# SCH_G-Cacher_2026-07-06.net
KiCad netlist of a schematic drawn in EasyEDA
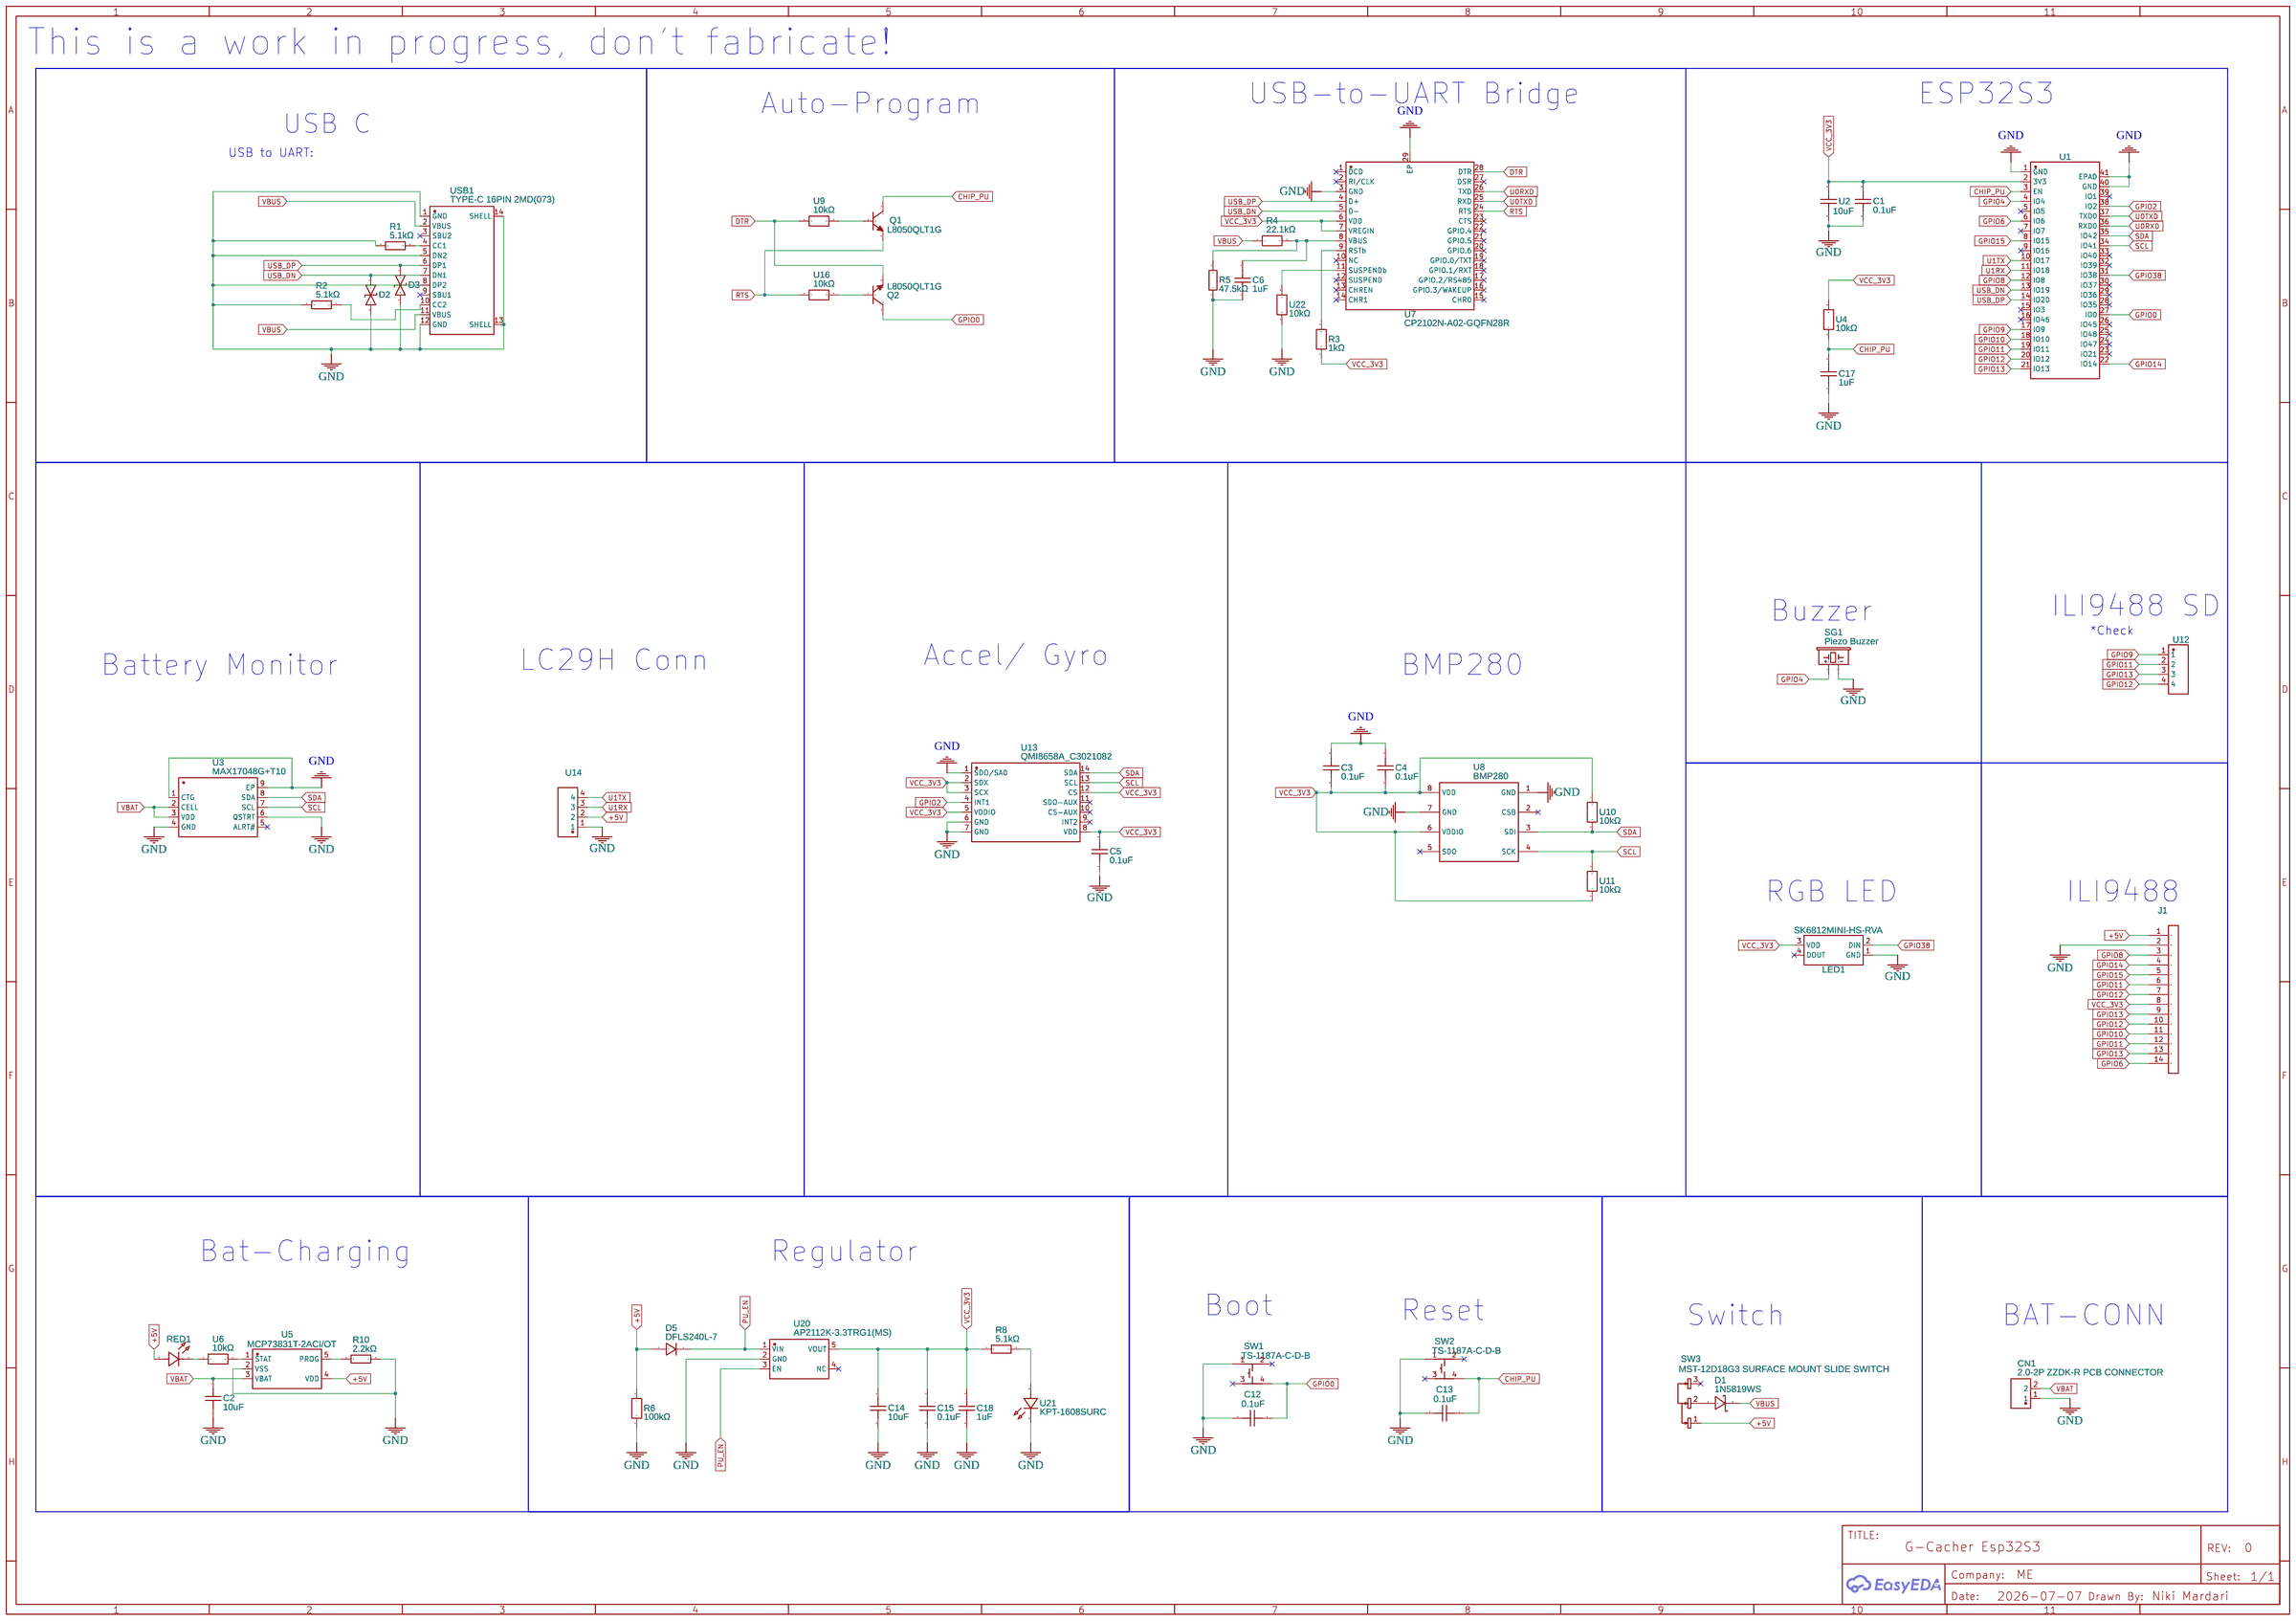
[diagram p0: schematic sheet]

(export (version "E")
  (design (tool "Eeschema 10.0.6"))
  (components
    (comp (ref "C1")
      (value "0.1uF")
      (fields (field (name "Manufacturer Part") "C1005X5R1E104M050BC") (field (name "Manufacturer") "TDK"))
      (libsource (lib "") (part "C1005X5R1E104M050BC_C3886291_1"))
    )
    (comp (ref "C2")
      (value "10uF")
      (fields (field (name "Manufacturer Part") "0603X106M100NT") (field (name "Manufacturer") "FH(风华)"))
      (libsource (lib "") (part "0603X106M100NT"))
    )
    (comp (ref "C3")
      (value "0.1uF")
      (fields (field (name "Manufacturer Part") "C1005X5R1E104M050BC") (field (name "Manufacturer") "TDK"))
      (libsource (lib "") (part "C1005X5R1E104M050BC_C3886291_1"))
    )
    (comp (ref "C4")
      (value "0.1uF")
      (fields (field (name "Manufacturer Part") "C1005X5R1E104M050BC") (field (name "Manufacturer") "TDK"))
      (libsource (lib "") (part "C1005X5R1E104M050BC_C3886291_1"))
    )
    (comp (ref "C5")
      (value "0.1uF")
      (fields (field (name "Manufacturer Part") "C1005X5R1E104M050BC") (field (name "Manufacturer") "TDK"))
      (libsource (lib "") (part "C1005X5R1E104M050BC_C3886291_1"))
    )
    (comp (ref "C6")
      (value "1uF")
      (fields (field (name "Manufacturer Part") "YNA18B3U0G105MT000N") (field (name "Manufacturer") "TDK"))
      (libsource (lib "") (part "YNA18B3U0G105MT000N"))
    )
    (comp (ref "C12")
      (value "0.1uF")
      (fields (field (name "Manufacturer Part") "C1005X5R1E104M050BC") (field (name "Manufacturer") "TDK"))
      (libsource (lib "") (part "C1005X5R1E104M050BC_C3886291"))
    )
    (comp (ref "C13")
      (value "0.1uF")
      (fields (field (name "Manufacturer Part") "C1005X5R1E104M050BC") (field (name "Manufacturer") "TDK"))
      (libsource (lib "") (part "C1005X5R1E104M050BC_C3886291"))
    )
    (comp (ref "C14")
      (value "10uF")
      (fields (field (name "Manufacturer Part") "0603X106M100NT") (field (name "Manufacturer") "FH(风华)"))
      (libsource (lib "") (part "0603X106M100NT"))
    )
    (comp (ref "C15")
      (value "0.1uF")
      (fields (field (name "Manufacturer Part") "C1005X5R1E104M050BC") (field (name "Manufacturer") "TDK"))
      (libsource (lib "") (part "C1005X5R1E104M050BC_C3886291_1"))
    )
    (comp (ref "C17")
      (value "1uF")
      (fields (field (name "Manufacturer Part") "YNA18B3U0G105MT000N") (field (name "Manufacturer") "TDK"))
      (libsource (lib "") (part "YNA18B3U0G105MT000N"))
    )
    (comp (ref "C18")
      (value "1uF")
      (fields (field (name "Manufacturer Part") "YNA18B3U0G105MT000N") (field (name "Manufacturer") "TDK"))
      (libsource (lib "") (part "YNA18B3U0G105MT000N"))
    )
    (comp (ref "CN1")
      (value "2.0-2P ZZDK-R PCB CONNECTOR")
      (fields
        (field (name "Manufacturer Part") "2.0-2P ZZDK-R PCB Connector")
        (field (name "Manufacturer") "SHOU HAN(首韩)")
      )
      (libsource (lib "") (part "2.0-2P ZZDK-R PCB CONNECTOR"))
    )
    (comp (ref "D1")
      (value "1N5819WS")
      (fields (field (name "Manufacturer") "Hottech(合科泰)"))
      (libsource (lib "") (part "1N5819WS"))
    )
    (comp (ref "D2")
      (value "LESD5D5.0CT1G")
      (fields (field (name "Manufacturer") "LRC(乐山无线电)"))
      (libsource (lib "") (part "LESD5D5.0CT1G"))
    )
    (comp (ref "D3")
      (value "LESD5D5.0CT1G")
      (fields (field (name "Manufacturer") "LRC(乐山无线电)"))
      (libsource (lib "") (part "LESD5D5.0CT1G"))
    )
    (comp (ref "D5")
      (value "DFLS240L-7")
      (fields (field (name "Manufacturer") "DIODES(美台)"))
      (libsource (lib "") (part "DFLS240L-7"))
    )
    (comp (ref "J1") (value "14 PIN FEMALE HEADER") (libsource (lib "") (part "14 PIN FEMALE HEADER")))
    (comp (ref "LED1")
      (value "SK6812MINI-HS-RVA")
      (fields (field (name "Manufacturer") "欧思科光电"))
      (libsource (lib "") (part "SK6812MINI-HS-RVA"))
    )
    (comp (ref "Q1")
      (value "L8050QLT1G")
      (fields (field (name "Manufacturer") "LRC(乐山无线电)"))
      (libsource (lib "") (part "L8050QLT1G_1"))
    )
    (comp (ref "Q2")
      (value "L8050QLT1G")
      (fields (field (name "Manufacturer") "LRC(乐山无线电)"))
      (libsource (lib "") (part "L8050QLT1G"))
    )
    (comp (ref "R1")
      (value "5.1kΩ")
      (fields
        (field (name "Manufacturer Part") "0402WGF5101TCE")
        (field (name "Manufacturer") "UNI-ROYAL(厚声)")
      )
      (libsource (lib "") (part "0402WGF5101TCE"))
    )
    (comp (ref "R2")
      (value "5.1kΩ")
      (fields
        (field (name "Manufacturer Part") "0402WGF5101TCE")
        (field (name "Manufacturer") "UNI-ROYAL(厚声)")
      )
      (libsource (lib "") (part "0402WGF5101TCE"))
    )
    (comp (ref "R3")
      (value "1kΩ")
      (fields (field (name "Manufacturer Part") "PTFR0603Q1K00N9") (field (name "Manufacturer") "RESI(开步睿思)"))
      (libsource (lib "") (part "PTFR0603Q1K00N9"))
    )
    (comp (ref "R4")
      (value "22.1kΩ")
      (fields (field (name "Manufacturer Part") "FRC0402F2212TS") (field (name "Manufacturer") "FOJAN(富捷)"))
      (libsource (lib "") (part "FRC0402F2212TS"))
    )
    (comp (ref "R5")
      (value "47.5kΩ")
      (fields (field (name "Manufacturer Part") "RC-02K4752FT") (field (name "Manufacturer") "FH(风华)"))
      (libsource (lib "") (part "RC-02K4752FT"))
    )
    (comp (ref "R6")
      (value "100kΩ")
      (fields
        (field (name "Manufacturer Part") "TR0603B100KP0525Z")
        (field (name "Manufacturer") "EVER OHMS(天二科技)")
      )
      (libsource (lib "") (part "TR0603B100KP0525Z"))
    )
    (comp (ref "R8")
      (value "5.1kΩ")
      (fields
        (field (name "Manufacturer Part") "0402WGF5101TCE")
        (field (name "Manufacturer") "UNI-ROYAL(厚声)")
      )
      (libsource (lib "") (part "0402WGF5101TCE"))
    )
    (comp (ref "R10")
      (value "2.2kΩ")
      (fields (field (name "Manufacturer Part") "RMC04022.2K5%N") (field (name "Manufacturer") "Tyohm(幸亚电阻)"))
      (libsource (lib "") (part "RMC04022.2K5%N"))
    )
    (comp (ref "RED1")
      (value "F.0603.00008/P2-0603R1TS2-06T-002")
      (fields (field (name "Manufacturer") "TUOZHAN(拓展光电)"))
      (libsource (lib "") (part "F.0603.00008/P2-0603R1TS2-06T-002"))
    )
    (comp (ref "SG1") (value "Piezo Buzzer") (libsource (lib "") (part "Piezo Buzzer")))
    (comp (ref "SW1")
      (value "TS-1187A-C-D-B")
      (fields (field (name "Manufacturer") "XKB Connection(中国星坤)"))
      (libsource (lib "") (part "TS-1187A-C-D-B"))
    )
    (comp (ref "SW2")
      (value "TS-1187A-C-D-B")
      (fields (field (name "Manufacturer") "XKB Connection(中国星坤)"))
      (libsource (lib "") (part "TS-1187A-C-D-B"))
    )
    (comp (ref "SW3")
      (value "MST-12D18G3 SURFACE MOUNT SLIDE SWITCH")
      (fields
        (field (name "Manufacturer Part") "MST-12D18G3 Surface Mount Slide Switch")
        (field (name "Manufacturer") "SHOU HAN(首韩)")
      )
      (libsource (lib "") (part "MST-12D18G3 SURFACE MOUNT SLIDE SWITCH"))
    )
    (comp (ref "U1") (value "ESPS3-32-WROOM-1-N16R8") (libsource (lib "") (part "ESPS3-32-WROOM-1-N16R8")))
    (comp (ref "U2")
      (value "10uF")
      (fields
        (field (name "Manufacturer Part") "HGC0603R5106K250NTHJ")
        (field (name "Manufacturer") "Chinocera(华瓷)")
      )
      (libsource (lib "") (part "HGC0603R5106K250NTHJ"))
    )
    (comp (ref "U3")
      (value "MAX17048G+T10")
      (fields (field (name "Manufacturer") "ADI(亚德诺)/MAXIM(美信)"))
      (libsource (lib "") (part "MAX17048G+T10"))
    )
    (comp (ref "U4")
      (value "10kΩ")
      (fields (field (name "Manufacturer Part") "THC02H1002BT") (field (name "Manufacturer") "FH(风华)"))
      (libsource (lib "") (part "THC02H1002BT"))
    )
    (comp (ref "U5")
      (value "MCP73831T-2ACI/OT")
      (fields (field (name "Manufacturer") "MICROCHIP(美国微芯)"))
      (libsource (lib "") (part "MCP73831T-2ACI/OT"))
    )
    (comp (ref "U6")
      (value "10kΩ")
      (fields
        (field (name "Manufacturer Part") "CRGH0603F10K")
        (field (name "Manufacturer") "TE Connectivity(泰科电子)")
      )
      (libsource (lib "") (part "CRGH0603F10K_1"))
    )
    (comp (ref "U7")
      (value "CP2102N-A02-GQFN28R")
      (fields (field (name "Manufacturer") "SKYWORKS/SILICON LABS(芯科)"))
      (libsource (lib "") (part "CP2102N-A02-GQFN28R"))
    )
    (comp (ref "U8")
      (value "BMP280")
      (fields (field (name "Manufacturer") "Bosch(博世)"))
      (libsource (lib "") (part "BMP280"))
    )
    (comp (ref "U9")
      (value "10kΩ")
      (fields
        (field (name "Manufacturer Part") "CRGH0603F10K")
        (field (name "Manufacturer") "TE Connectivity(泰科电子)")
      )
      (libsource (lib "") (part "CRGH0603F10K_2"))
    )
    (comp (ref "U10")
      (value "10kΩ")
      (fields
        (field (name "Manufacturer Part") "CRGH0603F10K")
        (field (name "Manufacturer") "TE Connectivity(泰科电子)")
      )
      (libsource (lib "") (part "CRGH0603F10K"))
    )
    (comp (ref "U11")
      (value "10kΩ")
      (fields
        (field (name "Manufacturer Part") "CRGH0603F10K")
        (field (name "Manufacturer") "TE Connectivity(泰科电子)")
      )
      (libsource (lib "") (part "CRGH0603F10K_3"))
    )
    (comp (ref "U12")
      (value "SSW-104-01-T-S")
      (fields (field (name "Manufacturer") "SAMTEC"))
      (libsource (lib "") (part "SSW-104-01-T-S"))
    )
    (comp (ref "U13")
      (value "QMI8658A_C3021082")
      (fields (field (name "Manufacturer Part") "QMI8658A") (field (name "Manufacturer") "QST(上海矽睿)"))
      (libsource (lib "") (part "QMI8658A_C3021082"))
    )
    (comp (ref "U14")
      (value "SSW-104-01-T-S")
      (fields (field (name "Manufacturer") "SAMTEC"))
      (libsource (lib "") (part "SSW-104-01-T-S_1"))
    )
    (comp (ref "U16")
      (value "10kΩ")
      (fields
        (field (name "Manufacturer Part") "CRGH0603F10K")
        (field (name "Manufacturer") "TE Connectivity(泰科电子)")
      )
      (libsource (lib "") (part "CRGH0603F10K_2"))
    )
    (comp (ref "U20")
      (value "AP2112K-3.3TRG1(MS)")
      (fields (field (name "Manufacturer") "MSKSEMI(美森科)"))
      (libsource (lib "") (part "AP2112K-3.3TRG1(MS)"))
    )
    (comp (ref "U21")
      (value "KPT-1608SURC")
      (fields (field (name "Manufacturer") "Kingbright"))
      (libsource (lib "") (part "KPT-1608SURC"))
    )
    (comp (ref "U22")
      (value "10kΩ")
      (fields
        (field (name "Manufacturer Part") "CRGH0603F10K")
        (field (name "Manufacturer") "TE Connectivity(泰科电子)")
      )
      (libsource (lib "") (part "CRGH0603F10K_3"))
    )
    (comp (ref "USB1")
      (value "TYPE-C 16PIN 2MD(073)")
      (fields (field (name "Manufacturer") "SHOU HAN(首韩)"))
      (libsource (lib "") (part "TYPE-C 16PIN 2MD(073)"))
    )
  )
  (nets
    (net (code "1") (name "+5V") (class "Default")
      (node (ref "D5") (pin "2") (pinfunction "2_2") (pintype "unspecified"))
      (node (ref "J1") (pin "1") (pinfunction "1_1") (pintype "unspecified"))
      (node (ref "R6") (pin "2") (pinfunction "2_2") (pintype "unspecified"))
      (node (ref "RED1") (pin "1") (pinfunction "+_1") (pintype "unspecified"))
      (node (ref "SW3") (pin "1") (pinfunction "1_1") (pintype "unspecified"))
      (node (ref "U14") (pin "2") (pinfunction "2_2") (pintype "unspecified"))
      (node (ref "U5") (pin "4") (pinfunction "VDD_4") (pintype "unspecified"))
    )
    (net (code "2") (name "CHIP_PU") (class "Default")
      (node (ref "C13") (pin "1") (pinfunction "1_1") (pintype "unspecified"))
      (node (ref "C17") (pin "2") (pinfunction "2_2") (pintype "unspecified"))
      (node (ref "Q1") (pin "3") (pinfunction "C_3") (pintype "unspecified"))
      (node (ref "SW2") (pin "4") (pinfunction "D_4") (pintype "unspecified"))
      (node (ref "U1") (pin "3") (pinfunction "EN_3") (pintype "unspecified"))
      (node (ref "U4") (pin "1") (pinfunction "1_1") (pintype "unspecified"))
    )
    (net (code "3") (name "DTR") (class "Default")
      (node (ref "Q2") (pin "2") (pinfunction "E_2") (pintype "unspecified"))
      (node (ref "U7") (pin "28") (pinfunction "DTR_28") (pintype "unspecified"))
      (node (ref "U9") (pin "1") (pinfunction "1_1") (pintype "unspecified"))
    )
    (net (code "4") (name "GND") (class "Default")
      (node (ref "C1") (pin "1") (pinfunction "1_1") (pintype "unspecified"))
      (node (ref "C12") (pin "2") (pinfunction "2_2") (pintype "unspecified"))
      (node (ref "C13") (pin "2") (pinfunction "2_2") (pintype "unspecified"))
      (node (ref "C14") (pin "1") (pinfunction "1_1") (pintype "unspecified"))
      (node (ref "C15") (pin "1") (pinfunction "1_1") (pintype "unspecified"))
      (node (ref "C17") (pin "1") (pinfunction "1_1") (pintype "unspecified"))
      (node (ref "C18") (pin "1") (pinfunction "1_1") (pintype "unspecified"))
      (node (ref "C2") (pin "1") (pinfunction "1_1") (pintype "unspecified"))
      (node (ref "C3") (pin "2") (pinfunction "2_2") (pintype "unspecified"))
      (node (ref "C4") (pin "2") (pinfunction "2_2") (pintype "unspecified"))
      (node (ref "C5") (pin "1") (pinfunction "1_1") (pintype "unspecified"))
      (node (ref "C6") (pin "1") (pinfunction "1_1") (pintype "unspecified"))
      (node (ref "CN1") (pin "1") (pinfunction "1_1") (pintype "unspecified"))
      (node (ref "D2") (pin "2") (pinfunction "2_2") (pintype "unspecified"))
      (node (ref "D3") (pin "2") (pinfunction "2_2") (pintype "unspecified"))
      (node (ref "J1") (pin "2") (pinfunction "2_2") (pintype "unspecified"))
      (node (ref "LED1") (pin "1") (pinfunction "GND_1") (pintype "unspecified"))
      (node (ref "R1") (pin "1") (pinfunction "1_1") (pintype "input"))
      (node (ref "R10") (pin "1") (pinfunction "1_1") (pintype "unspecified"))
      (node (ref "R2") (pin "1") (pinfunction "1_1") (pintype "input"))
      (node (ref "R5") (pin "1") (pinfunction "1_1") (pintype "unspecified"))
      (node (ref "R6") (pin "1") (pinfunction "1_1") (pintype "unspecified"))
      (node (ref "SG1") (pin "-") (pinfunction "2_-") (pintype "unspecified"))
      (node (ref "SW1") (pin "1") (pinfunction "A_1") (pintype "unspecified"))
      (node (ref "SW2") (pin "1") (pinfunction "A_1") (pintype "unspecified"))
      (node (ref "U1") (pin "1") (pinfunction "GND_1") (pintype "unspecified"))
      (node (ref "U1") (pin "40") (pinfunction "GND_40") (pintype "unspecified"))
      (node (ref "U1") (pin "41") (pinfunction "EPAD_41") (pintype "unspecified"))
      (node (ref "U13") (pin "1") (pinfunction "SDO/SA0_1") (pintype "unspecified"))
      (node (ref "U13") (pin "6") (pinfunction "GND_6") (pintype "unspecified"))
      (node (ref "U13") (pin "7") (pinfunction "GND_7") (pintype "unspecified"))
      (node (ref "U14") (pin "1") (pinfunction "1_1") (pintype "unspecified"))
      (node (ref "U2") (pin "1") (pinfunction "1_1") (pintype "unspecified"))
      (node (ref "U20") (pin "2") (pinfunction "GND_2") (pintype "unspecified"))
      (node (ref "U21") (pin "1") (pinfunction "K_1") (pintype "unspecified"))
      (node (ref "U22") (pin "1") (pinfunction "1_1") (pintype "unspecified"))
      (node (ref "U3") (pin "1") (pinfunction "CTG_1") (pintype "unspecified"))
      (node (ref "U3") (pin "4") (pinfunction "GND_4") (pintype "unspecified"))
      (node (ref "U3") (pin "6") (pinfunction "QSTRT_6") (pintype "unspecified"))
      (node (ref "U3") (pin "9") (pinfunction "EP_9") (pintype "unspecified"))
      (node (ref "U5") (pin "2") (pinfunction "VSS_2") (pintype "unspecified"))
      (node (ref "U7") (pin "29") (pinfunction "EP_29") (pintype "unspecified"))
      (node (ref "U7") (pin "3") (pinfunction "GND_3") (pintype "unspecified"))
      (node (ref "U8") (pin "1") (pinfunction "GND_1") (pintype "unspecified"))
      (node (ref "U8") (pin "7") (pinfunction "GND_7") (pintype "unspecified"))
      (node (ref "USB1") (pin "1") (pinfunction "GND_1") (pintype "unspecified"))
      (node (ref "USB1") (pin "12") (pinfunction "GND_12") (pintype "unspecified"))
      (node (ref "USB1") (pin "13") (pinfunction "SHELL_13") (pintype "unspecified"))
      (node (ref "USB1") (pin "14") (pinfunction "SHELL_14") (pintype "unspecified"))
      (node (ref "USB1") (pin "5") (pinfunction "DN2_5") (pintype "unspecified"))
      (node (ref "USB1") (pin "8") (pinfunction "DP2_8") (pintype "unspecified"))
    )
    (net (code "5") (name "GPIO0") (class "Default")
      (node (ref "C12") (pin "1") (pinfunction "1_1") (pintype "unspecified"))
      (node (ref "Q2") (pin "3") (pinfunction "C_3") (pintype "unspecified"))
      (node (ref "SW1") (pin "4") (pinfunction "D_4") (pintype "unspecified"))
      (node (ref "U1") (pin "27") (pinfunction "IO0_27") (pintype "unspecified"))
    )
    (net (code "6") (name "GPIO2") (class "Default")
      (node (ref "U1") (pin "38") (pinfunction "IO2_38") (pintype "unspecified"))
      (node (ref "U13") (pin "4") (pinfunction "INT1_4") (pintype "unspecified"))
    )
    (net (code "7") (name "GPIO4") (class "Default")
      (node (ref "SG1") (pin "+") (pinfunction "1_+") (pintype "unspecified"))
      (node (ref "U1") (pin "4") (pinfunction "IO4_4") (pintype "unspecified"))
    )
    (net (code "8") (name "GPIO6") (class "Default")
      (node (ref "J1") (pin "14") (pinfunction "14_14") (pintype "unspecified"))
      (node (ref "U1") (pin "6") (pinfunction "IO6_6") (pintype "unspecified"))
    )
    (net (code "9") (name "GPIO8") (class "Default")
      (node (ref "J1") (pin "3") (pinfunction "3_3") (pintype "unspecified"))
      (node (ref "U1") (pin "12") (pinfunction "IO8_12") (pintype "unspecified"))
    )
    (net (code "10") (name "GPIO9") (class "Default")
      (node (ref "U1") (pin "17") (pinfunction "IO9_17") (pintype "unspecified"))
      (node (ref "U12") (pin "1") (pinfunction "1_1") (pintype "unspecified"))
    )
    (net (code "11") (name "GPIO10") (class "Default")
      (node (ref "J1") (pin "11") (pinfunction "11_11") (pintype "unspecified"))
      (node (ref "U1") (pin "18") (pinfunction "IO10_18") (pintype "unspecified"))
    )
    (net (code "12") (name "GPIO11") (class "Default")
      (node (ref "J1") (pin "12") (pinfunction "12_12") (pintype "unspecified"))
      (node (ref "J1") (pin "6") (pinfunction "6_6") (pintype "unspecified"))
      (node (ref "U1") (pin "19") (pinfunction "IO11_19") (pintype "unspecified"))
      (node (ref "U12") (pin "2") (pinfunction "2_2") (pintype "unspecified"))
    )
    (net (code "13") (name "GPIO12") (class "Default")
      (node (ref "J1") (pin "10") (pinfunction "10_10") (pintype "unspecified"))
      (node (ref "J1") (pin "7") (pinfunction "7_7") (pintype "unspecified"))
      (node (ref "U1") (pin "20") (pinfunction "IO12_20") (pintype "unspecified"))
      (node (ref "U12") (pin "4") (pinfunction "4_4") (pintype "unspecified"))
    )
    (net (code "14") (name "GPIO13") (class "Default")
      (node (ref "J1") (pin "13") (pinfunction "13_13") (pintype "unspecified"))
      (node (ref "J1") (pin "9") (pinfunction "9_9") (pintype "unspecified"))
      (node (ref "U1") (pin "21") (pinfunction "IO13_21") (pintype "unspecified"))
      (node (ref "U12") (pin "3") (pinfunction "3_3") (pintype "unspecified"))
    )
    (net (code "15") (name "GPIO14") (class "Default")
      (node (ref "J1") (pin "4") (pinfunction "4_4") (pintype "unspecified"))
      (node (ref "U1") (pin "22") (pinfunction "IO14_22") (pintype "unspecified"))
    )
    (net (code "16") (name "GPIO15") (class "Default")
      (node (ref "J1") (pin "5") (pinfunction "5_5") (pintype "unspecified"))
      (node (ref "U1") (pin "8") (pinfunction "IO15_8") (pintype "unspecified"))
    )
    (net (code "17") (name "GPIO38") (class "Default")
      (node (ref "LED1") (pin "2") (pinfunction "DIN_2") (pintype "unspecified"))
      (node (ref "U1") (pin "31") (pinfunction "IO38_31") (pintype "unspecified"))
    )
    (net (code "18") (name "Net-(D1-A)") (class "Default")
      (node (ref "D1") (pin "2") (pinfunction "A_2") (pintype "unspecified"))
      (node (ref "SW3") (pin "2") (pinfunction "2_2") (pintype "unspecified"))
    )
    (net (code "19") (name "Net-(Q1-B)") (class "Default")
      (node (ref "Q1") (pin "1") (pinfunction "B_1") (pintype "unspecified"))
      (node (ref "U9") (pin "2") (pinfunction "2_2") (pintype "unspecified"))
    )
    (net (code "20") (name "Net-(Q2-B)") (class "Default")
      (node (ref "Q2") (pin "1") (pinfunction "B_1") (pintype "unspecified"))
      (node (ref "U16") (pin "2") (pinfunction "2_2") (pintype "unspecified"))
    )
    (net (code "21") (name "Net-(RED1--)") (class "Default")
      (node (ref "RED1") (pin "2") (pinfunction "-_2") (pintype "unspecified"))
      (node (ref "U6") (pin "2") (pinfunction "2_2") (pintype "unspecified"))
    )
    (net (code "22") (name "Net-(U5-PROG)") (class "Default")
      (node (ref "R10") (pin "2") (pinfunction "2_2") (pintype "unspecified"))
      (node (ref "U5") (pin "5") (pinfunction "PROG_5") (pintype "unspecified"))
    )
    (net (code "23") (name "Net-(U5-STAT)") (class "Default")
      (node (ref "U5") (pin "1") (pinfunction "STAT_1") (pintype "unspecified"))
      (node (ref "U6") (pin "1") (pinfunction "1_1") (pintype "unspecified"))
    )
    (net (code "24") (name "Net-(U7-RSTb)") (class "Default")
      (node (ref "R3") (pin "2") (pinfunction "2_2") (pintype "unspecified"))
      (node (ref "U7") (pin "9") (pinfunction "RSTb_9") (pintype "unspecified"))
    )
    (net (code "25") (name "Net-(U7-SUSPENDb)") (class "Default")
      (node (ref "U22") (pin "2") (pinfunction "2_2") (pintype "unspecified"))
      (node (ref "U7") (pin "11") (pinfunction "SUSPENDb_11") (pintype "unspecified"))
    )
    (net (code "26") (name "Net-(U7-VBUS)") (class "Default")
      (node (ref "C6") (pin "2") (pinfunction "2_2") (pintype "unspecified"))
      (node (ref "R4") (pin "2") (pinfunction "2_2") (pintype "unspecified"))
      (node (ref "R5") (pin "2") (pinfunction "2_2") (pintype "unspecified"))
      (node (ref "U7") (pin "8") (pinfunction "VBUS_8") (pintype "unspecified"))
    )
    (net (code "27") (name "Net-(U21-A)") (class "Default")
      (node (ref "R8") (pin "2") (pinfunction "2_2") (pintype "input"))
      (node (ref "U21") (pin "2") (pinfunction "A_2") (pintype "unspecified"))
    )
    (net (code "28") (name "Net-(USB1-CC1)") (class "Default")
      (node (ref "R1") (pin "2") (pinfunction "2_2") (pintype "input"))
      (node (ref "USB1") (pin "4") (pinfunction "CC1_4") (pintype "unspecified"))
    )
    (net (code "29") (name "Net-(USB1-CC2)") (class "Default")
      (node (ref "R2") (pin "2") (pinfunction "2_2") (pintype "input"))
      (node (ref "USB1") (pin "10") (pinfunction "CC2_10") (pintype "unspecified"))
    )
    (net (code "30") (name "PU_EN") (class "Default")
      (node (ref "D5") (pin "1") (pinfunction "1_1") (pintype "unspecified"))
      (node (ref "U20") (pin "1") (pinfunction "VIN_1") (pintype "unspecified"))
      (node (ref "U20") (pin "3") (pinfunction "EN_3") (pintype "unspecified"))
    )
    (net (code "31") (name "RTS") (class "Default")
      (node (ref "Q1") (pin "2") (pinfunction "E_2") (pintype "unspecified"))
      (node (ref "U16") (pin "1") (pinfunction "1_1") (pintype "unspecified"))
      (node (ref "U7") (pin "24") (pinfunction "RTS_24") (pintype "unspecified"))
    )
    (net (code "32") (name "SCL") (class "Default")
      (node (ref "U1") (pin "34") (pinfunction "IO41_34") (pintype "unspecified"))
      (node (ref "U11") (pin "2") (pinfunction "2_2") (pintype "unspecified"))
      (node (ref "U13") (pin "13") (pinfunction "SCL_13") (pintype "unspecified"))
      (node (ref "U3") (pin "7") (pinfunction "SCL_7") (pintype "unspecified"))
      (node (ref "U8") (pin "4") (pinfunction "SCK_4") (pintype "unspecified"))
    )
    (net (code "33") (name "SDA") (class "Default")
      (node (ref "U1") (pin "35") (pinfunction "IO42_35") (pintype "unspecified"))
      (node (ref "U10") (pin "2") (pinfunction "2_2") (pintype "unspecified"))
      (node (ref "U13") (pin "14") (pinfunction "SDA_14") (pintype "unspecified"))
      (node (ref "U3") (pin "8") (pinfunction "SDA_8") (pintype "unspecified"))
      (node (ref "U8") (pin "3") (pinfunction "SDI_3") (pintype "unspecified"))
    )
    (net (code "34") (name "U0RXD") (class "Default")
      (node (ref "U1") (pin "36") (pinfunction "RXD0_36") (pintype "unspecified"))
      (node (ref "U7") (pin "26") (pinfunction "TXD_26") (pintype "unspecified"))
    )
    (net (code "35") (name "U0TXD") (class "Default")
      (node (ref "U1") (pin "37") (pinfunction "TXD0_37") (pintype "unspecified"))
      (node (ref "U7") (pin "25") (pinfunction "RXD_25") (pintype "unspecified"))
    )
    (net (code "36") (name "U1RX") (class "Default")
      (node (ref "U1") (pin "11") (pinfunction "IO18_11") (pintype "unspecified"))
      (node (ref "U14") (pin "3") (pinfunction "3_3") (pintype "unspecified"))
    )
    (net (code "37") (name "U1TX") (class "Default")
      (node (ref "U1") (pin "10") (pinfunction "IO17_10") (pintype "unspecified"))
      (node (ref "U14") (pin "4") (pinfunction "4_4") (pintype "unspecified"))
    )
    (net (code "38") (name "USB_DN") (class "Default")
      (node (ref "D2") (pin "1") (pinfunction "1_1") (pintype "unspecified"))
      (node (ref "U1") (pin "13") (pinfunction "IO19_13") (pintype "unspecified"))
      (node (ref "U7") (pin "5") (pinfunction "D-_5") (pintype "unspecified"))
      (node (ref "USB1") (pin "7") (pinfunction "DN1_7") (pintype "unspecified"))
    )
    (net (code "39") (name "USB_DP") (class "Default")
      (node (ref "D3") (pin "1") (pinfunction "1_1") (pintype "unspecified"))
      (node (ref "U1") (pin "14") (pinfunction "IO20_14") (pintype "unspecified"))
      (node (ref "U7") (pin "4") (pinfunction "D+_4") (pintype "unspecified"))
      (node (ref "USB1") (pin "6") (pinfunction "DP1_6") (pintype "unspecified"))
    )
    (net (code "40") (name "VBAT") (class "Default")
      (node (ref "C2") (pin "2") (pinfunction "2_2") (pintype "unspecified"))
      (node (ref "CN1") (pin "2") (pinfunction "2_2") (pintype "unspecified"))
      (node (ref "U3") (pin "2") (pinfunction "CELL_2") (pintype "unspecified"))
      (node (ref "U3") (pin "3") (pinfunction "VDD_3") (pintype "unspecified"))
      (node (ref "U5") (pin "3") (pinfunction "VBAT_3") (pintype "unspecified"))
    )
    (net (code "41") (name "VBUS") (class "Default")
      (node (ref "D1") (pin "1") (pinfunction "K_1") (pintype "unspecified"))
      (node (ref "R4") (pin "1") (pinfunction "1_1") (pintype "unspecified"))
      (node (ref "USB1") (pin "11") (pinfunction "VBUS_11") (pintype "unspecified"))
      (node (ref "USB1") (pin "2") (pinfunction "VBUS_2") (pintype "unspecified"))
    )
    (net (code "42") (name "VCC_3V3") (class "Default")
      (node (ref "C1") (pin "2") (pinfunction "2_2") (pintype "unspecified"))
      (node (ref "C14") (pin "2") (pinfunction "2_2") (pintype "unspecified"))
      (node (ref "C15") (pin "2") (pinfunction "2_2") (pintype "unspecified"))
      (node (ref "C18") (pin "2") (pinfunction "2_2") (pintype "unspecified"))
      (node (ref "C3") (pin "1") (pinfunction "1_1") (pintype "unspecified"))
      (node (ref "C4") (pin "1") (pinfunction "1_1") (pintype "unspecified"))
      (node (ref "C5") (pin "2") (pinfunction "2_2") (pintype "unspecified"))
      (node (ref "J1") (pin "8") (pinfunction "8_8") (pintype "unspecified"))
      (node (ref "LED1") (pin "3") (pinfunction "VDD_3") (pintype "unspecified"))
      (node (ref "R3") (pin "1") (pinfunction "1_1") (pintype "unspecified"))
      (node (ref "R8") (pin "1") (pinfunction "1_1") (pintype "input"))
      (node (ref "U1") (pin "2") (pinfunction "3V3_2") (pintype "unspecified"))
      (node (ref "U10") (pin "1") (pinfunction "1_1") (pintype "unspecified"))
      (node (ref "U11") (pin "1") (pinfunction "1_1") (pintype "unspecified"))
      (node (ref "U13") (pin "12") (pinfunction "CS_12") (pintype "unspecified"))
      (node (ref "U13") (pin "2") (pinfunction "SDX_2") (pintype "unspecified"))
      (node (ref "U13") (pin "3") (pinfunction "SCX_3") (pintype "unspecified"))
      (node (ref "U13") (pin "5") (pinfunction "VDDIO_5") (pintype "unspecified"))
      (node (ref "U13") (pin "8") (pinfunction "VDD_8") (pintype "unspecified"))
      (node (ref "U2") (pin "2") (pinfunction "2_2") (pintype "unspecified"))
      (node (ref "U20") (pin "5") (pinfunction "VOUT_5") (pintype "unspecified"))
      (node (ref "U4") (pin "2") (pinfunction "2_2") (pintype "unspecified"))
      (node (ref "U7") (pin "6") (pinfunction "VDD_6") (pintype "unspecified"))
      (node (ref "U7") (pin "7") (pinfunction "VREGIN_7") (pintype "unspecified"))
      (node (ref "U8") (pin "6") (pinfunction "VDDIO_6") (pintype "unspecified"))
      (node (ref "U8") (pin "8") (pinfunction "VDD_8") (pintype "unspecified"))
    )
    (net (code "43") (name "unconnected-(LED1-DOUT-Pad4)") (class "Default")
      (node (ref "LED1") (pin "4") (pinfunction "DOUT_4") (pintype "unspecified+no_connect"))
    )
    (net (code "44") (name "unconnected-(SW1-B-Pad2)") (class "Default")
      (node (ref "SW1") (pin "2") (pinfunction "B_2") (pintype "unspecified+no_connect"))
    )
    (net (code "45") (name "unconnected-(SW1-C-Pad3)") (class "Default")
      (node (ref "SW1") (pin "3") (pinfunction "C_3") (pintype "unspecified+no_connect"))
    )
    (net (code "46") (name "unconnected-(SW2-B-Pad2)") (class "Default")
      (node (ref "SW2") (pin "2") (pinfunction "B_2") (pintype "unspecified+no_connect"))
    )
    (net (code "47") (name "unconnected-(SW2-C-Pad3)") (class "Default")
      (node (ref "SW2") (pin "3") (pinfunction "C_3") (pintype "unspecified+no_connect"))
    )
    (net (code "48") (name "unconnected-(SW3-Pad3)") (class "Default")
      (node (ref "SW3") (pin "3") (pinfunction "3_3") (pintype "unspecified+no_connect"))
    )
    (net (code "49") (name "unconnected-(U1-IO1-Pad39)") (class "Default")
      (node (ref "U1") (pin "39") (pinfunction "IO1_39") (pintype "unspecified+no_connect"))
    )
    (net (code "50") (name "unconnected-(U1-IO3-Pad15)") (class "Default")
      (node (ref "U1") (pin "15") (pinfunction "IO3_15") (pintype "unspecified+no_connect"))
    )
    (net (code "51") (name "unconnected-(U1-IO5-Pad5)") (class "Default")
      (node (ref "U1") (pin "5") (pinfunction "IO5_5") (pintype "unspecified+no_connect"))
    )
    (net (code "52") (name "unconnected-(U1-IO7-Pad7)") (class "Default")
      (node (ref "U1") (pin "7") (pinfunction "IO7_7") (pintype "unspecified+no_connect"))
    )
    (net (code "53") (name "unconnected-(U1-IO16-Pad9)") (class "Default")
      (node (ref "U1") (pin "9") (pinfunction "IO16_9") (pintype "unspecified+no_connect"))
    )
    (net (code "54") (name "unconnected-(U1-IO21-Pad23)") (class "Default")
      (node (ref "U1") (pin "23") (pinfunction "IO21_23") (pintype "unspecified+no_connect"))
    )
    (net (code "55") (name "unconnected-(U1-IO35-Pad28)") (class "Default")
      (node (ref "U1") (pin "28") (pinfunction "IO35_28") (pintype "unspecified+no_connect"))
    )
    (net (code "56") (name "unconnected-(U1-IO36-Pad29)") (class "Default")
      (node (ref "U1") (pin "29") (pinfunction "IO36_29") (pintype "unspecified+no_connect"))
    )
    (net (code "57") (name "unconnected-(U1-IO37-Pad30)") (class "Default")
      (node (ref "U1") (pin "30") (pinfunction "IO37_30") (pintype "unspecified+no_connect"))
    )
    (net (code "58") (name "unconnected-(U1-IO39-Pad32)") (class "Default")
      (node (ref "U1") (pin "32") (pinfunction "IO39_32") (pintype "unspecified+no_connect"))
    )
    (net (code "59") (name "unconnected-(U1-IO40-Pad33)") (class "Default")
      (node (ref "U1") (pin "33") (pinfunction "IO40_33") (pintype "unspecified+no_connect"))
    )
    (net (code "60") (name "unconnected-(U1-IO45-Pad26)") (class "Default")
      (node (ref "U1") (pin "26") (pinfunction "IO45_26") (pintype "unspecified+no_connect"))
    )
    (net (code "61") (name "unconnected-(U1-IO46-Pad16)") (class "Default")
      (node (ref "U1") (pin "16") (pinfunction "IO46_16") (pintype "unspecified+no_connect"))
    )
    (net (code "62") (name "unconnected-(U1-IO47-Pad24)") (class "Default")
      (node (ref "U1") (pin "24") (pinfunction "IO47_24") (pintype "unspecified+no_connect"))
    )
    (net (code "63") (name "unconnected-(U1-IO48-Pad25)") (class "Default")
      (node (ref "U1") (pin "25") (pinfunction "IO48_25") (pintype "unspecified+no_connect"))
    )
    (net (code "64") (name "unconnected-(U3-ALRT#-Pad5)") (class "Default")
      (node (ref "U3") (pin "5") (pinfunction "ALRT#_5") (pintype "unspecified+no_connect"))
    )
    (net (code "65") (name "unconnected-(U7-CHR0-Pad15)") (class "Default")
      (node (ref "U7") (pin "15") (pinfunction "CHR0_15") (pintype "unspecified+no_connect"))
    )
    (net (code "66") (name "unconnected-(U7-CHR1-Pad14)") (class "Default")
      (node (ref "U7") (pin "14") (pinfunction "CHR1_14") (pintype "unspecified+no_connect"))
    )
    (net (code "67") (name "unconnected-(U7-CHREN-Pad13)") (class "Default")
      (node (ref "U7") (pin "13") (pinfunction "CHREN_13") (pintype "unspecified+no_connect"))
    )
    (net (code "68") (name "unconnected-(U7-CTS-Pad23)") (class "Default")
      (node (ref "U7") (pin "23") (pinfunction "CTS_23") (pintype "unspecified+no_connect"))
    )
    (net (code "69") (name "unconnected-(U7-DCD-Pad1)") (class "Default")
      (node (ref "U7") (pin "1") (pinfunction "DCD_1") (pintype "unspecified+no_connect"))
    )
    (net (code "70") (name "unconnected-(U7-DSR-Pad27)") (class "Default")
      (node (ref "U7") (pin "27") (pinfunction "DSR_27") (pintype "unspecified+no_connect"))
    )
    (net (code "71") (name "unconnected-(U7-GPIO.0{slash}TXT-Pad19)") (class "Default")
      (node (ref "U7") (pin "19") (pinfunction "GPIO.0/TXT_19") (pintype "unspecified+no_connect"))
    )
    (net (code "72") (name "unconnected-(U7-GPIO.1{slash}RXT-Pad18)") (class "Default")
      (node (ref "U7") (pin "18") (pinfunction "GPIO.1/RXT_18") (pintype "unspecified+no_connect"))
    )
    (net (code "73") (name "unconnected-(U7-GPIO.2{slash}RS485-Pad17)") (class "Default")
      (node (ref "U7") (pin "17") (pinfunction "GPIO.2/RS485_17") (pintype "unspecified+no_connect"))
    )
    (net (code "74") (name "unconnected-(U7-GPIO.3{slash}WAKEUP-Pad16)") (class "Default")
      (node (ref "U7") (pin "16") (pinfunction "GPIO.3/WAKEUP_16") (pintype "unspecified+no_connect"))
    )
    (net (code "75") (name "unconnected-(U7-GPIO.4-Pad22)") (class "Default")
      (node (ref "U7") (pin "22") (pinfunction "GPIO.4_22") (pintype "unspecified+no_connect"))
    )
    (net (code "76") (name "unconnected-(U7-GPIO.5-Pad21)") (class "Default")
      (node (ref "U7") (pin "21") (pinfunction "GPIO.5_21") (pintype "unspecified+no_connect"))
    )
    (net (code "77") (name "unconnected-(U7-GPIO.6-Pad20)") (class "Default")
      (node (ref "U7") (pin "20") (pinfunction "GPIO.6_20") (pintype "unspecified+no_connect"))
    )
    (net (code "78") (name "unconnected-(U7-NC-Pad10)") (class "Default")
      (node (ref "U7") (pin "10") (pinfunction "NC_10") (pintype "unspecified+no_connect"))
    )
    (net (code "79") (name "unconnected-(U7-RI{slash}CLK-Pad2)") (class "Default")
      (node (ref "U7") (pin "2") (pinfunction "RI/CLK_2") (pintype "unspecified+no_connect"))
    )
    (net (code "80") (name "unconnected-(U7-SUSPEND-Pad12)") (class "Default")
      (node (ref "U7") (pin "12") (pinfunction "SUSPEND_12") (pintype "unspecified+no_connect"))
    )
    (net (code "81") (name "unconnected-(U8-CSB-Pad2)") (class "Default")
      (node (ref "U8") (pin "2") (pinfunction "CSB_2") (pintype "unspecified+no_connect"))
    )
    (net (code "82") (name "unconnected-(U8-SDO-Pad5)") (class "Default")
      (node (ref "U8") (pin "5") (pinfunction "SDO_5") (pintype "unspecified+no_connect"))
    )
    (net (code "83") (name "unconnected-(U13-CS-AUX-Pad10)") (class "Default")
      (node (ref "U13") (pin "10") (pinfunction "CS-AUX_10") (pintype "unspecified+no_connect"))
    )
    (net (code "84") (name "unconnected-(U13-INT2-Pad9)") (class "Default")
      (node (ref "U13") (pin "9") (pinfunction "INT2_9") (pintype "unspecified+no_connect"))
    )
    (net (code "85") (name "unconnected-(U13-SDO-AUX-Pad11)") (class "Default")
      (node (ref "U13") (pin "11") (pinfunction "SDO-AUX_11") (pintype "unspecified+no_connect"))
    )
    (net (code "86") (name "unconnected-(U20-NC-Pad4)") (class "Default")
      (node (ref "U20") (pin "4") (pinfunction "NC_4") (pintype "unspecified+no_connect"))
    )
    (net (code "87") (name "unconnected-(USB1-SBU1-Pad9)") (class "Default")
      (node (ref "USB1") (pin "9") (pinfunction "SBU1_9") (pintype "unspecified+no_connect"))
    )
    (net (code "88") (name "unconnected-(USB1-SBU2-Pad3)") (class "Default")
      (node (ref "USB1") (pin "3") (pinfunction "SBU2_3") (pintype "unspecified+no_connect"))
    )
  )
)
